# Half_Slave.net
KiCad netlist of a schematic drawn in Altium Designer
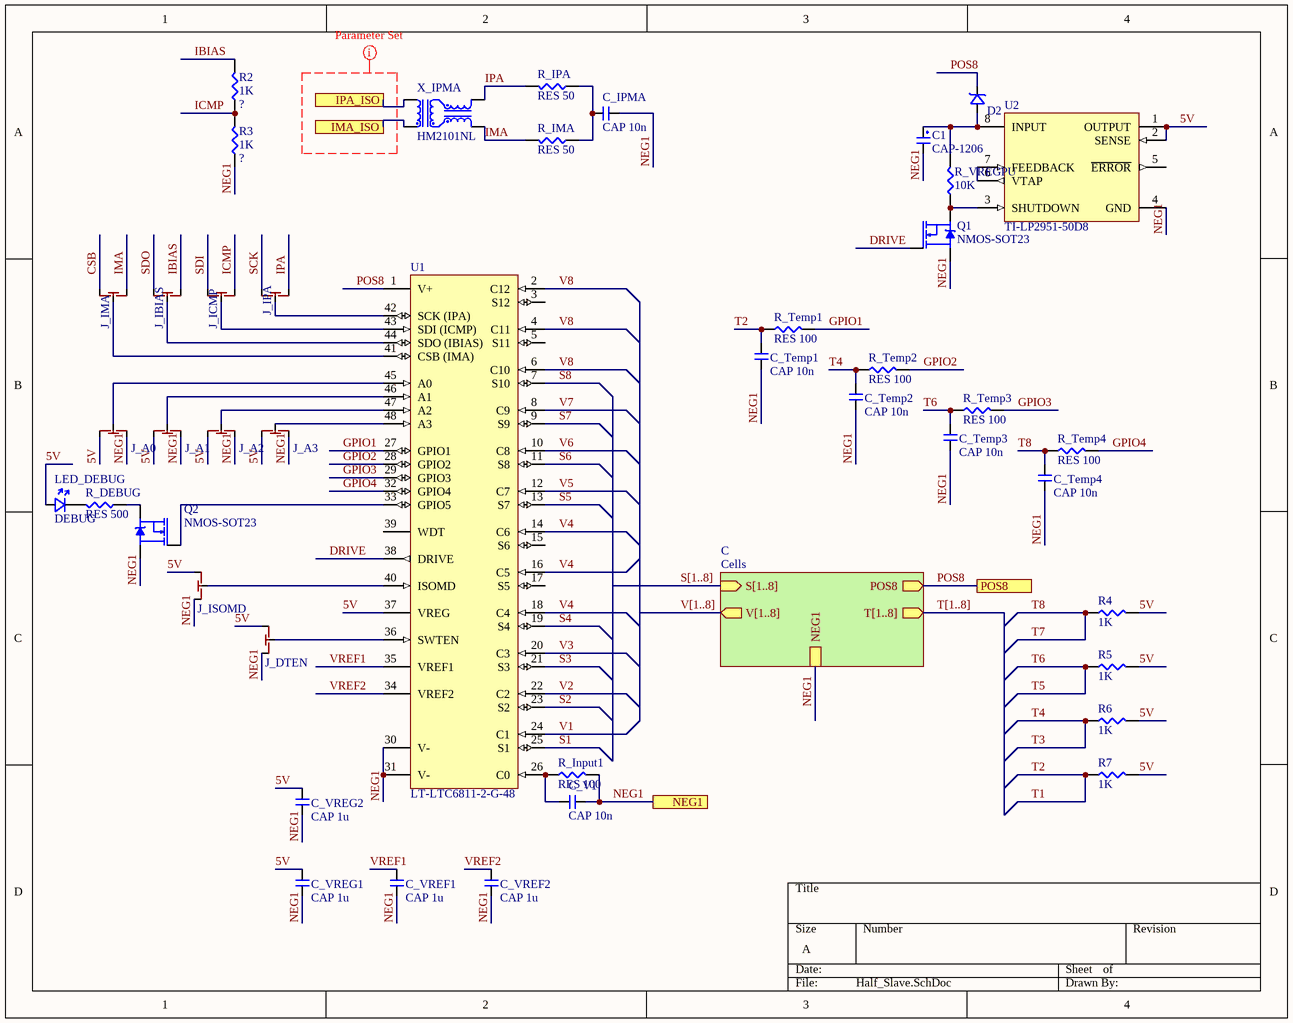
[diagram p0: Half_Slave.SchDoc]

(export (version "E")
  (design (tool "Eeschema 10.0.6"))
  (components
    (comp (ref "C1")
      (value "CAP-1206")
      (footprint "CAPCP3216X16N")
      (libsource (lib "LTC6811") (part "CAP-1206"))
    )
    (comp (ref "C_IPMA")
      (value "CAP 10n")
      (footprint "CAP-0603")
      (description "CAP-0603")
      (libsource (lib "ife18_TS_BMS_LTC6813_v2_Library") (part "CAP-0603"))
    )
    (comp (ref "C_Temp1")
      (value "CAP 10n")
      (footprint "CAP-0603")
      (description "CAP-0603")
      (libsource (lib "altium-import") (part "root_1_CAP-0603_"))
    )
    (comp (ref "C_Temp2")
      (value "CAP 10n")
      (footprint "CAP-0603")
      (description "CAP-0603")
      (libsource (lib "altium-import") (part "root_1_CAP-0603_"))
    )
    (comp (ref "C_Temp3")
      (value "CAP 10n")
      (footprint "CAP-0603")
      (description "CAP-0603")
      (libsource (lib "altium-import") (part "root_1_CAP-0603_"))
    )
    (comp (ref "C_Temp4")
      (value "CAP 10n")
      (footprint "CAP-0603")
      (description "CAP-0603")
      (libsource (lib "altium-import") (part "root_1_CAP-0603_"))
    )
    (comp (ref "C_V1")
      (value "CAP 10n")
      (footprint "CAP-0603")
      (description "CAP-0603")
      (libsource (lib "altium-import") (part "root_2_CAP-0603_"))
    )
    (comp (ref "C_VREF1")
      (value "CAP 1u")
      (footprint "CAP-0603")
      (description "CAP-0603")
      (libsource (lib "altium-import") (part "root_1_CAP-0603_"))
    )
    (comp (ref "C_VREF2")
      (value "CAP 1u")
      (footprint "CAP-0603")
      (description "CAP-0603")
      (libsource (lib "altium-import") (part "root_1_CAP-0603_"))
    )
    (comp (ref "C_VREG1")
      (value "CAP 1u")
      (footprint "CAP-0603")
      (description "CAP-0603")
      (libsource (lib "altium-import") (part "root_1_CAP-0603_"))
    )
    (comp (ref "C_VREG2")
      (value "CAP 1u")
      (footprint "CAP-0603")
      (description "CAP-0603")
      (libsource (lib "altium-import") (part "root_1_CAP-0603_"))
    )
    (comp (ref "D2") (value "?") (footprint "SMB") (libsource (lib "ife19_Elec_Library") (part "DIODE-SMB")))
    (comp (ref "J_A0")
      (value "DPDT Solder Jumper")
      (footprint "DPDT Solder")
      (libsource (lib "LTC6811") (part "DPDT Solder"))
    )
    (comp (ref "J_A1")
      (value "DPDT Solder Jumper")
      (footprint "DPDT Solder")
      (libsource (lib "LTC6811") (part "DPDT Solder"))
    )
    (comp (ref "J_A2")
      (value "DPDT Solder Jumper")
      (footprint "DPDT Solder")
      (libsource (lib "LTC6811") (part "DPDT Solder"))
    )
    (comp (ref "J_A3")
      (value "DPDT Solder Jumper")
      (footprint "DPDT Solder")
      (libsource (lib "LTC6811") (part "DPDT Solder"))
    )
    (comp (ref "J_DTEN")
      (value "DPDT Solder Jumper")
      (footprint "DPDT Solder")
      (libsource (lib "LTC6811") (part "DPDT Solder"))
    )
    (comp (ref "J_IBIAS")
      (value "DPDT Solder Jumper")
      (footprint "DPDT Solder")
      (libsource (lib "LTC6811") (part "DPDT Solder"))
    )
    (comp (ref "J_ICMP")
      (value "DPDT Solder Jumper")
      (footprint "DPDT Solder")
      (libsource (lib "LTC6811") (part "DPDT Solder"))
    )
    (comp (ref "J_IMA")
      (value "DPDT Solder Jumper")
      (footprint "DPDT Solder")
      (libsource (lib "LTC6811") (part "DPDT Solder"))
    )
    (comp (ref "J_IPA")
      (value "DPDT Solder Jumper")
      (footprint "DPDT Solder")
      (libsource (lib "LTC6811") (part "DPDT Solder"))
    )
    (comp (ref "J_ISOMD")
      (value "DPDT Solder Jumper")
      (footprint "DPDT Solder")
      (libsource (lib "LTC6811") (part "DPDT Solder"))
    )
    (comp (ref "LED_DEBUG")
      (value "DEBUG")
      (footprint "LED-0603")
      (description "LED-0603")
      (libsource (lib "altium-import") (part "root_0_LED-0603_"))
    )
    (comp (ref "Q1")
      (value "NMOS-SOT23")
      (footprint "SOT23")
      (libsource (lib "ife19_Elec_Library") (part "NMOS-SOT23"))
    )
    (comp (ref "Q2")
      (value "NMOS-SOT23")
      (footprint "SOT23")
      (libsource (lib "ife19_Elec_Library") (part "NMOS-SOT23"))
    )
    (comp (ref "R2")
      (value "1K")
      (footprint "RES-0603")
      (description "RES SMD 0603")
      (fields (field (name "PART") "RES_0603") (field (name "ALTIUM_VALUE") "?"))
      (libsource (lib "IFE") (part "RES"))
    )
    (comp (ref "R3")
      (value "1K")
      (footprint "RES-0603")
      (description "RES SMD 0603")
      (fields (field (name "PART") "RES_0603") (field (name "ALTIUM_VALUE") "?"))
      (libsource (lib "IFE") (part "RES"))
    )
    (comp (ref "R4")
      (value "1K")
      (footprint "RES-0603")
      (libsource (lib "ife19_Elec_Library") (part "RES-0603"))
    )
    (comp (ref "R5")
      (value "1K")
      (footprint "RES-0603")
      (libsource (lib "ife19_Elec_Library") (part "RES-0603"))
    )
    (comp (ref "R6")
      (value "1K")
      (footprint "RES-0603")
      (libsource (lib "ife19_Elec_Library") (part "RES-0603"))
    )
    (comp (ref "R7")
      (value "1K")
      (footprint "RES-0603")
      (libsource (lib "ife19_Elec_Library") (part "RES-0603"))
    )
    (comp (ref "R_DEBUG")
      (value "RES 500")
      (footprint "RES-0603")
      (libsource (lib "altium-import") (part "root_2_RES-0603_"))
    )
    (comp (ref "R_IMA")
      (value "RES 50")
      (footprint "RES-0603")
      (libsource (lib "ife18_TS_BMS_LTC6813_v2_Library") (part "RES-0603"))
    )
    (comp (ref "R_Input1")
      (value "RES 100")
      (footprint "RES-0603")
      (libsource (lib "altium-import") (part "root_0_RES-0603_"))
    )
    (comp (ref "R_IPA")
      (value "RES 50")
      (footprint "RES-0603")
      (libsource (lib "ife18_TS_BMS_LTC6813_v2_Library") (part "RES-0603"))
    )
    (comp (ref "R_Temp1")
      (value "RES 100")
      (footprint "RES-0603")
      (libsource (lib "altium-import") (part "root_0_RES-0603_"))
    )
    (comp (ref "R_Temp2")
      (value "RES 100")
      (footprint "RES-0603")
      (libsource (lib "altium-import") (part "root_0_RES-0603_"))
    )
    (comp (ref "R_Temp3")
      (value "RES 100")
      (footprint "RES-0603")
      (libsource (lib "altium-import") (part "root_0_RES-0603_"))
    )
    (comp (ref "R_Temp4")
      (value "RES 100")
      (footprint "RES-0603")
      (libsource (lib "altium-import") (part "root_0_RES-0603_"))
    )
    (comp (ref "R_VREGPU")
      (value "10K")
      (footprint "RES-0603")
      (libsource (lib "ife18_TS_BMS_LTC6813_v2_Library") (part "RES-0603"))
    )
    (comp (ref "U1")
      (value "LT-LTC6811-2-G-48")
      (footprint "SSOP-48N")
      (libsource (lib "LTC6811") (part "LT-LTC6811-2-G-48"))
    )
    (comp (ref "U2")
      (value "TI-LP2951-50D8")
      (footprint "SOIC127P600X175-8N")
      (libsource (lib "LTC6811") (part "TI-LP2951-50D8"))
    )
    (comp (ref "X_IPMA")
      (value "HM2101NL")
      (footprint "HM2101")
      (libsource (lib "altium-import") (part "root_2_HM2101NL_"))
    )
  )
  (nets
    (net (code "1") (name "/5V") (class "Default")
      (node (ref "C_VREG1") (pin "2") (pinfunction "2_2") (pintype "passive"))
      (node (ref "C_VREG2") (pin "2") (pinfunction "2_2") (pintype "passive"))
      (node (ref "J_A0") (pin "2") (pintype "passive"))
      (node (ref "J_A1") (pin "2") (pintype "passive"))
      (node (ref "J_A2") (pin "2") (pintype "passive"))
      (node (ref "J_A3") (pin "2") (pintype "passive"))
      (node (ref "J_DTEN") (pin "2") (pintype "passive"))
      (node (ref "J_ISOMD") (pin "2") (pintype "passive"))
      (node (ref "LED_DEBUG") (pin "A") (pinfunction "A_A") (pintype "passive"))
      (node (ref "R4") (pin "2") (pinfunction "2_2") (pintype "passive"))
      (node (ref "R5") (pin "2") (pinfunction "2_2") (pintype "passive"))
      (node (ref "R6") (pin "2") (pinfunction "2_2") (pintype "passive"))
      (node (ref "R7") (pin "2") (pinfunction "2_2") (pintype "passive"))
      (node (ref "U1") (pin "37") (pinfunction "VREG_37") (pintype "power_in"))
      (node (ref "U2") (pin "1") (pinfunction "OUTPUT_1") (pintype "power_in"))
      (node (ref "U2") (pin "2") (pinfunction "SENSE_2") (pintype "input"))
    )
    (net (code "2") (name "/CSB") (class "Default") (node (ref "J_IMA") (pin "1") (pintype "passive")))
    (net (code "3") (name "/DRIVE") (class "Default")
      (node (ref "Q1") (pin "1") (pinfunction "G_1") (pintype "passive"))
      (node (ref "U1") (pin "38") (pinfunction "DRIVE_38") (pintype "output"))
    )
    (net (code "4") (name "/GPIO1") (class "Default")
      (node (ref "R_Temp1") (pin "2") (pinfunction "2_2") (pintype "passive"))
      (node (ref "U1") (pin "27") (pinfunction "GPIO1_27") (pintype "bidirectional"))
    )
    (net (code "5") (name "/GPIO2") (class "Default")
      (node (ref "R_Temp2") (pin "2") (pinfunction "2_2") (pintype "passive"))
      (node (ref "U1") (pin "28") (pinfunction "GPIO2_28") (pintype "bidirectional"))
    )
    (net (code "6") (name "/GPIO3") (class "Default")
      (node (ref "R_Temp3") (pin "2") (pinfunction "2_2") (pintype "passive"))
      (node (ref "U1") (pin "29") (pinfunction "GPIO3_29") (pintype "bidirectional"))
    )
    (net (code "7") (name "/GPIO4") (class "Default")
      (node (ref "R_Temp4") (pin "2") (pinfunction "2_2") (pintype "passive"))
      (node (ref "U1") (pin "32") (pinfunction "GPIO4_32") (pintype "bidirectional"))
    )
    (net (code "8") (name "/IBIAS") (class "Default")
      (node (ref "J_IBIAS") (pin "2") (pintype "passive"))
      (node (ref "R2") (pin "2") (pinfunction "2_2") (pintype "passive"))
    )
    (net (code "9") (name "/ICMP") (class "Default")
      (node (ref "J_ICMP") (pin "2") (pintype "passive"))
      (node (ref "R2") (pin "1") (pinfunction "1_1") (pintype "passive"))
      (node (ref "R3") (pin "2") (pinfunction "2_2") (pintype "passive"))
    )
    (net (code "10") (name "/IMA") (class "Default")
      (node (ref "J_IMA") (pin "2") (pintype "passive"))
      (node (ref "R_IMA") (pin "2") (pinfunction "2_2") (pintype "passive"))
      (node (ref "X_IPMA") (pin "4") (pinfunction "4_4") (pintype "passive"))
    )
    (net (code "11") (name "/IMA_ISO") (class "Default")
      (node (ref "X_IPMA") (pin "3") (pinfunction "3_3") (pintype "passive"))
    )
    (net (code "12") (name "/IPA") (class "Default")
      (node (ref "J_IPA") (pin "2") (pintype "passive"))
      (node (ref "R_IPA") (pin "2") (pinfunction "2_2") (pintype "passive"))
      (node (ref "X_IPMA") (pin "6") (pinfunction "6_6") (pintype "passive"))
    )
    (net (code "13") (name "/IPA_ISO") (class "Default")
      (node (ref "X_IPMA") (pin "1") (pinfunction "1_1") (pintype "passive"))
    )
    (net (code "14") (name "/NEG1") (class "Default")
      (node (ref "C1") (pin "2") (pinfunction "2_2") (pintype "passive"))
      (node (ref "C_IPMA") (pin "1") (pinfunction "1_1") (pintype "passive"))
      (node (ref "C_Temp1") (pin "1") (pinfunction "1_1") (pintype "passive"))
      (node (ref "C_Temp2") (pin "1") (pinfunction "1_1") (pintype "passive"))
      (node (ref "C_Temp3") (pin "1") (pinfunction "1_1") (pintype "passive"))
      (node (ref "C_Temp4") (pin "1") (pinfunction "1_1") (pintype "passive"))
      (node (ref "C_V1") (pin "1") (pinfunction "1_1") (pintype "passive"))
      (node (ref "C_VREF1") (pin "1") (pinfunction "1_1") (pintype "passive"))
      (node (ref "C_VREF2") (pin "1") (pinfunction "1_1") (pintype "passive"))
      (node (ref "C_VREG1") (pin "1") (pinfunction "1_1") (pintype "passive"))
      (node (ref "C_VREG2") (pin "1") (pinfunction "1_1") (pintype "passive"))
      (node (ref "J_A0") (pin "1") (pintype "passive"))
      (node (ref "J_A1") (pin "1") (pintype "passive"))
      (node (ref "J_A2") (pin "1") (pintype "passive"))
      (node (ref "J_A3") (pin "1") (pintype "passive"))
      (node (ref "J_DTEN") (pin "1") (pintype "passive"))
      (node (ref "J_ISOMD") (pin "1") (pintype "passive"))
      (node (ref "Q1") (pin "2") (pinfunction "S_2") (pintype "passive"))
      (node (ref "Q2") (pin "2") (pinfunction "S_2") (pintype "passive"))
      (node (ref "R3") (pin "1") (pinfunction "1_1") (pintype "passive"))
      (node (ref "R_Input1") (pin "2") (pinfunction "2_2") (pintype "passive"))
      (node (ref "U1") (pin "30") (pinfunction "V-_30") (pintype "power_in"))
      (node (ref "U1") (pin "31") (pinfunction "V-_31") (pintype "power_in"))
      (node (ref "U2") (pin "4") (pinfunction "GND_4") (pintype "power_in"))
    )
    (net (code "15") (name "/POS8") (class "Default")
      (node (ref "D2") (pin "K") (pinfunction "K_K") (pintype "passive"))
      (node (ref "U1") (pin "1") (pinfunction "V+_1") (pintype "power_in"))
    )
    (net (code "16") (name "/S1") (class "Default")
      (node (ref "U1") (pin "25") (pinfunction "S1_25") (pintype "bidirectional"))
    )
    (net (code "17") (name "/S2") (class "Default")
      (node (ref "U1") (pin "23") (pinfunction "S2_23") (pintype "bidirectional"))
    )
    (net (code "18") (name "/S3") (class "Default")
      (node (ref "U1") (pin "21") (pinfunction "S3_21") (pintype "bidirectional"))
    )
    (net (code "19") (name "/S4") (class "Default")
      (node (ref "U1") (pin "19") (pinfunction "S4_19") (pintype "bidirectional"))
    )
    (net (code "20") (name "/S5") (class "Default")
      (node (ref "U1") (pin "13") (pinfunction "S7_13") (pintype "bidirectional"))
    )
    (net (code "21") (name "/S6") (class "Default")
      (node (ref "U1") (pin "11") (pinfunction "S8_11") (pintype "bidirectional"))
    )
    (net (code "22") (name "/S7") (class "Default")
      (node (ref "U1") (pin "9") (pinfunction "S9_9") (pintype "bidirectional"))
    )
    (net (code "23") (name "/S8") (class "Default")
      (node (ref "U1") (pin "7") (pinfunction "S10_7") (pintype "bidirectional"))
    )
    (net (code "24") (name "/SCK") (class "Default") (node (ref "J_IPA") (pin "1") (pintype "passive")))
    (net (code "25") (name "/SDI") (class "Default") (node (ref "J_ICMP") (pin "1") (pintype "passive")))
    (net (code "26") (name "/SDO") (class "Default") (node (ref "J_IBIAS") (pin "1") (pintype "passive")))
    (net (code "28") (name "/T2") (class "Default")
      (node (ref "C_Temp1") (pin "2") (pinfunction "2_2") (pintype "passive"))
      (node (ref "R7") (pin "1") (pinfunction "1_1") (pintype "passive"))
      (node (ref "R_Temp1") (pin "1") (pinfunction "1_1") (pintype "passive"))
    )
    (net (code "29") (name "/T4") (class "Default")
      (node (ref "C_Temp2") (pin "2") (pinfunction "2_2") (pintype "passive"))
      (node (ref "R6") (pin "1") (pinfunction "1_1") (pintype "passive"))
      (node (ref "R_Temp2") (pin "1") (pinfunction "1_1") (pintype "passive"))
    )
    (net (code "30") (name "/T6") (class "Default")
      (node (ref "C_Temp3") (pin "2") (pinfunction "2_2") (pintype "passive"))
      (node (ref "R5") (pin "1") (pinfunction "1_1") (pintype "passive"))
      (node (ref "R_Temp3") (pin "1") (pinfunction "1_1") (pintype "passive"))
    )
    (net (code "31") (name "/T8") (class "Default")
      (node (ref "C_Temp4") (pin "2") (pinfunction "2_2") (pintype "passive"))
      (node (ref "R4") (pin "1") (pinfunction "1_1") (pintype "passive"))
      (node (ref "R_Temp4") (pin "1") (pinfunction "1_1") (pintype "passive"))
    )
    (net (code "33") (name "/V1") (class "Default")
      (node (ref "U1") (pin "24") (pinfunction "C1_24") (pintype "input"))
    )
    (net (code "34") (name "/V2") (class "Default")
      (node (ref "U1") (pin "22") (pinfunction "C2_22") (pintype "input"))
    )
    (net (code "35") (name "/V3") (class "Default")
      (node (ref "U1") (pin "20") (pinfunction "C3_20") (pintype "input"))
    )
    (net (code "36") (name "/V4") (class "Default")
      (node (ref "U1") (pin "14") (pinfunction "C6_14") (pintype "input"))
      (node (ref "U1") (pin "16") (pinfunction "C5_16") (pintype "input"))
      (node (ref "U1") (pin "18") (pinfunction "C4_18") (pintype "input"))
    )
    (net (code "37") (name "/V5") (class "Default")
      (node (ref "U1") (pin "12") (pinfunction "C7_12") (pintype "input"))
    )
    (net (code "38") (name "/V6") (class "Default")
      (node (ref "U1") (pin "10") (pinfunction "C8_10") (pintype "input"))
    )
    (net (code "39") (name "/V7") (class "Default")
      (node (ref "U1") (pin "8") (pinfunction "C9_8") (pintype "input"))
    )
    (net (code "40") (name "/V8") (class "Default")
      (node (ref "U1") (pin "2") (pinfunction "C12_2") (pintype "input"))
      (node (ref "U1") (pin "4") (pinfunction "C11_4") (pintype "input"))
      (node (ref "U1") (pin "6") (pinfunction "C10_6") (pintype "input"))
    )
    (net (code "41") (name "/VREF1") (class "Default")
      (node (ref "C_VREF1") (pin "2") (pinfunction "2_2") (pintype "passive"))
      (node (ref "U1") (pin "35") (pinfunction "VREF1_35") (pintype "passive"))
    )
    (net (code "42") (name "/VREF2") (class "Default")
      (node (ref "C_VREF2") (pin "2") (pinfunction "2_2") (pintype "passive"))
      (node (ref "U1") (pin "34") (pinfunction "VREF2_34") (pintype "passive"))
    )
    (net (code "44") (name "Net-(C_IPMA-Pad2)") (class "Default")
      (node (ref "C_IPMA") (pin "2") (pinfunction "2_2") (pintype "passive"))
      (node (ref "R_IMA") (pin "1") (pinfunction "1_1") (pintype "passive"))
      (node (ref "R_IPA") (pin "1") (pinfunction "1_1") (pintype "passive"))
    )
    (net (code "45") (name "Net-(LED_DEBUG-PadK)") (class "Default")
      (node (ref "LED_DEBUG") (pin "K") (pinfunction "K_K") (pintype "passive"))
      (node (ref "R_DEBUG") (pin "2") (pinfunction "2_2") (pintype "passive"))
    )
    (net (code "46") (name "Net-(Q1-D)") (class "Default")
      (node (ref "Q1") (pin "3") (pinfunction "D_3") (pintype "passive"))
      (node (ref "R_VREGPU") (pin "1") (pinfunction "1_1") (pintype "passive"))
      (node (ref "U2") (pin "3") (pinfunction "SHUTDOWN_3") (pintype "input"))
    )
    (net (code "47") (name "Net-(Q2-D)") (class "Default")
      (node (ref "Q2") (pin "3") (pinfunction "D_3") (pintype "passive"))
      (node (ref "R_DEBUG") (pin "1") (pinfunction "1_1") (pintype "passive"))
    )
    (net (code "48") (name "Net-(Q2-G)") (class "Default")
      (node (ref "Q2") (pin "1") (pinfunction "G_1") (pintype "passive"))
      (node (ref "U1") (pin "33") (pinfunction "GPIO5_33") (pintype "bidirectional"))
    )
    (net (code "49") (name "Net-(U1-A0)") (class "Default")
      (node (ref "J_A0") (pin "3") (pintype "passive"))
      (node (ref "U1") (pin "45") (pinfunction "A0_45") (pintype "input"))
    )
    (net (code "50") (name "Net-(U1-A1)") (class "Default")
      (node (ref "J_A1") (pin "3") (pintype "passive"))
      (node (ref "U1") (pin "46") (pinfunction "A1_46") (pintype "input"))
    )
    (net (code "51") (name "Net-(U1-A2)") (class "Default")
      (node (ref "J_A2") (pin "3") (pintype "passive"))
      (node (ref "U1") (pin "47") (pinfunction "A2_47") (pintype "input"))
    )
    (net (code "52") (name "Net-(U1-A3)") (class "Default")
      (node (ref "J_A3") (pin "3") (pintype "passive"))
      (node (ref "U1") (pin "48") (pinfunction "A3_48") (pintype "input"))
    )
    (net (code "53") (name "Net-(U1-C0)") (class "Default")
      (node (ref "C_V1") (pin "2") (pinfunction "2_2") (pintype "passive"))
      (node (ref "R_Input1") (pin "1") (pinfunction "1_1") (pintype "passive"))
      (node (ref "U1") (pin "26") (pinfunction "C0_26") (pintype "input"))
    )
    (net (code "54") (name "Net-(U1-CSB_(IMA))") (class "Default")
      (node (ref "J_IMA") (pin "3") (pintype "passive"))
      (node (ref "U1") (pin "41") (pinfunction "CSB_(IMA)_41") (pintype "bidirectional"))
    )
    (net (code "55") (name "Net-(U1-ISOMD)") (class "Default")
      (node (ref "J_ISOMD") (pin "3") (pintype "passive"))
      (node (ref "U1") (pin "40") (pinfunction "ISOMD_40") (pintype "input"))
    )
    (net (code "56") (name "Net-(U1-SCK_(IPA))") (class "Default")
      (node (ref "J_IPA") (pin "3") (pintype "passive"))
      (node (ref "U1") (pin "42") (pinfunction "SCK_(IPA)_42") (pintype "bidirectional"))
    )
    (net (code "57") (name "Net-(U1-SDI_(ICMP))") (class "Default")
      (node (ref "J_ICMP") (pin "3") (pintype "passive"))
      (node (ref "U1") (pin "43") (pinfunction "SDI_(ICMP)_43") (pintype "input"))
    )
    (net (code "58") (name "Net-(U1-SDO_(IBIAS))") (class "Default")
      (node (ref "J_IBIAS") (pin "3") (pintype "passive"))
      (node (ref "U1") (pin "44") (pinfunction "SDO_(IBIAS)_44") (pintype "bidirectional"))
    )
    (net (code "59") (name "Net-(U1-SWTEN)") (class "Default")
      (node (ref "J_DTEN") (pin "3") (pintype "passive"))
      (node (ref "U1") (pin "36") (pinfunction "SWTEN_36") (pintype "input"))
    )
    (net (code "60") (name "Net-(U2-FEEDBACK)") (class "Default")
      (node (ref "U2") (pin "6") (pinfunction "VTAP_6") (pintype "output"))
      (node (ref "U2") (pin "7") (pinfunction "FEEDBACK_7") (pintype "input"))
    )
    (net (code "61") (name "Net-(U2-INPUT)") (class "Default")
      (node (ref "C1") (pin "1") (pinfunction "1_1") (pintype "passive"))
      (node (ref "D2") (pin "A") (pinfunction "A_A") (pintype "passive"))
      (node (ref "R_VREGPU") (pin "2") (pinfunction "2_2") (pintype "passive"))
      (node (ref "U2") (pin "8") (pinfunction "INPUT_8") (pintype "power_in"))
    )
    (net (code "62") (name "unconnected-(U1-S5-Pad17)") (class "Default")
      (node (ref "U1") (pin "17") (pinfunction "S5_17") (pintype "bidirectional"))
    )
    (net (code "63") (name "unconnected-(U1-S6-Pad15)") (class "Default")
      (node (ref "U1") (pin "15") (pinfunction "S6_15") (pintype "bidirectional"))
    )
    (net (code "64") (name "unconnected-(U1-S11-Pad5)") (class "Default")
      (node (ref "U1") (pin "5") (pinfunction "S11_5") (pintype "bidirectional"))
    )
    (net (code "65") (name "unconnected-(U1-S12-Pad3)") (class "Default")
      (node (ref "U1") (pin "3") (pinfunction "S12_3") (pintype "bidirectional"))
    )
    (net (code "66") (name "unconnected-(U1-WDT-Pad39)") (class "Default")
      (node (ref "U1") (pin "39") (pinfunction "WDT_39") (pintype "tri_state"))
    )
    (net (code "67") (name "unconnected-(U2-~{ERROR}-Pad5)") (class "Default")
      (node (ref "U2") (pin "5") (pinfunction "~{ERROR}_5") (pintype "output"))
    )
  )
)
